# MicroController.net
KiCad netlist of a schematic drawn in Altium Designer
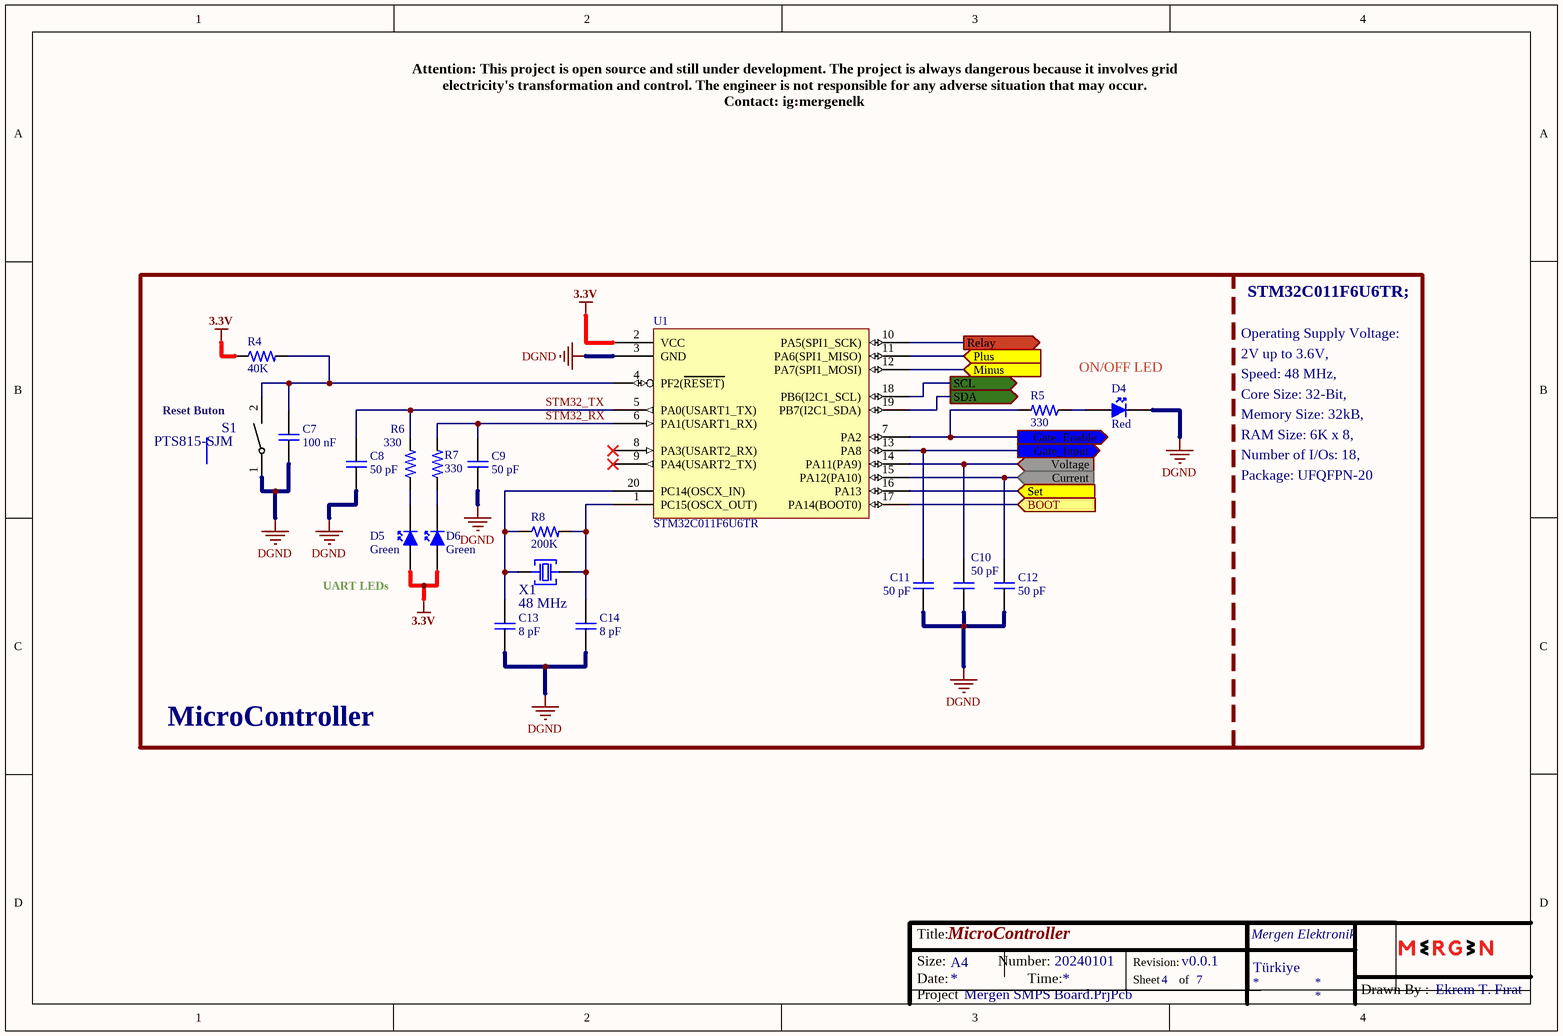
[diagram p0: MicroController.SchDoc]

(export (version "E")
  (design (tool "Eeschema 10.0.6"))
  (components
    (comp (ref "C7")
      (value "100 nF")
      (footprint "MergenElektronik_Capacitors_Ceramics_SMDs_0603_S_NS")
      (description "Mergen Elektronik - Capacitors - Ceramics - SMDs - 0603 - 100 nF - 16V")
      (fields (field (name "MANUFACTURER") "Samsung Electro-Mechanics") (field (name "TOLERANCE") "±10%"))
      (libsource (lib "MergenElektronik_Capacitors_Ceramics_SMDs") (part "MergenElektronik_Capacitors_Ceramic_SMDs_100nF_16V"))
    )
    (comp (ref "C8")
      (value "50 pF")
      (footprint "MergenElektronik_Capacitors_Ceramics_SMDs_0402_S_NS")
      (description "Mergen Elektronik - Capacitors - Ceramics - SMDs - 0402 - 50 pF - 50V")
      (fields (field (name "MANUFACTURER") "YAGEO") (field (name "TOLERANCE") "±5%"))
      (libsource (lib "MergenElektronik_Capacitors_Ceramics_SMDs") (part "MergenElektronik_Capacitors_Ceramic_SMDs_50pF_50V"))
    )
    (comp (ref "C9")
      (value "50 pF")
      (footprint "MergenElektronik_Capacitors_Ceramics_SMDs_0402_S_NS")
      (description "Mergen Elektronik - Capacitors - Ceramics - SMDs - 0402 - 50 pF - 50V")
      (fields (field (name "MANUFACTURER") "YAGEO") (field (name "TOLERANCE") "±5%"))
      (libsource (lib "MergenElektronik_Capacitors_Ceramics_SMDs") (part "MergenElektronik_Capacitors_Ceramic_SMDs_50pF_50V"))
    )
    (comp (ref "C10")
      (value "50 pF")
      (footprint "MergenElektronik_Capacitors_Ceramics_SMDs_0402_S_NS")
      (description "Mergen Elektronik - Capacitors - Ceramics - SMDs - 0402 - 50 pF - 50V")
      (fields (field (name "MANUFACTURER") "YAGEO") (field (name "TOLERANCE") "±5%"))
      (libsource (lib "MergenElektronik_Capacitors_Ceramics_SMDs") (part "MergenElektronik_Capacitors_Ceramic_SMDs_50pF_50V"))
    )
    (comp (ref "C11")
      (value "50 pF")
      (footprint "MergenElektronik_Capacitors_Ceramics_SMDs_0402_S_NS")
      (description "Mergen Elektronik - Capacitors - Ceramics - SMDs - 0402 - 50 pF - 50V")
      (fields (field (name "MANUFACTURER") "YAGEO") (field (name "TOLERANCE") "±5%"))
      (libsource (lib "MergenElektronik_Capacitors_Ceramics_SMDs") (part "MergenElektronik_Capacitors_Ceramic_SMDs_50pF_50V"))
    )
    (comp (ref "C12")
      (value "50 pF")
      (footprint "MergenElektronik_Capacitors_Ceramics_SMDs_0402_S_NS")
      (description "Mergen Elektronik - Capacitors - Ceramics - SMDs - 0402 - 50 pF - 50V")
      (fields (field (name "MANUFACTURER") "YAGEO") (field (name "TOLERANCE") "±5%"))
      (libsource (lib "MergenElektronik_Capacitors_Ceramics_SMDs") (part "MergenElektronik_Capacitors_Ceramic_SMDs_50pF_50V"))
    )
    (comp (ref "C13")
      (value "8 pF")
      (footprint "MergenElektronik_Capacitors_Ceramics_SMDs_0603_S_NS")
      (description "Mergen Elektronik - Capacitors - Ceramics - SMDs - 0603 - 8 pF - 50V")
      (fields (field (name "MANUFACTURER") "YAGEO") (field (name "TOLERANCE") "±0.5pF"))
      (libsource (lib "MergenElektronik_Capacitors_Ceramics_SMDs") (part "MergenElektronik_Capacitors_Ceramic_SMDs_8pF_50V"))
    )
    (comp (ref "C14")
      (value "8 pF")
      (footprint "MergenElektronik_Capacitors_Ceramics_SMDs_0603_S_NS")
      (description "Mergen Elektronik - Capacitors - Ceramics - SMDs - 0603 - 8 pF - 50V")
      (fields (field (name "MANUFACTURER") "YAGEO") (field (name "TOLERANCE") "±0.5pF"))
      (libsource (lib "MergenElektronik_Capacitors_Ceramics_SMDs") (part "MergenElektronik_Capacitors_Ceramic_SMDs_8pF_50V"))
    )
    (comp (ref "D4")
      (value "Red")
      (footprint "MergenElektronik_Leds_SMDs_0603_S")
      (description "Mergen Elektronik - Leds - SMDs - Red - 0603")
      (fields (field (name "MANUFACTURER") "Würth Elektronik"))
      (libsource (lib "MergenElektronik_Leds_SMDs") (part "MergenElektronik_LEDs_SMDs_Red_0603"))
    )
    (comp (ref "D5")
      (value "Green")
      (footprint "MergenElektronik_Leds_SMDs_0603_S")
      (description "Mergen Elektronik - Leds - SMDs - Green - 0603")
      (fields (field (name "MANUFACTURER") "Würth Elektronik"))
      (libsource (lib "MergenElektronik_Leds_SMDs") (part "MergenElektronik_LEDs_SMDs_Green_0603"))
    )
    (comp (ref "D6")
      (value "Green")
      (footprint "MergenElektronik_Leds_SMDs_0603_S")
      (description "Mergen Elektronik - Leds - SMDs - Green - 0603")
      (fields (field (name "MANUFACTURER") "Würth Elektronik"))
      (libsource (lib "MergenElektronik_Leds_SMDs") (part "MergenElektronik_LEDs_SMDs_Green_0603"))
    )
    (comp (ref "R4")
      (value "40K")
      (footprint "MergenElektronik_Resistors_ChipResistors_0603_S_NS")
      (description "Mergen Elektronik - Resistors - Chip Resistors - 0603 - 40K")
      (fields (field (name "MANUFACTURER") "YAGEO") (field (name "POWER") "1/10W"))
      (libsource (lib "MergenElektronik_Resistors_ChipResistors") (part "MergenElektronik_Resistors_ChipResistors_0603_40K"))
    )
    (comp (ref "R5")
      (value "330")
      (footprint "MergenElektronik_Resistors_ChipResistors_0603_S_NS")
      (description "Mergen Elektronik - Resistors - Chip Resistors - 0603 - 330R")
      (fields (field (name "MANUFACTURER") "Stackpole Electronics Inc") (field (name "POWER") "1/10W"))
      (libsource (lib "MergenElektronik_Resistors_ChipResistors") (part "MergenElektronik_Resistors_ChipResistors_0603_330R"))
    )
    (comp (ref "R6")
      (value "330")
      (footprint "MergenElektronik_Resistors_ChipResistors_0603_S_NS")
      (description "Mergen Elektronik - Resistors - Chip Resistors - 0603 - 330R")
      (fields (field (name "MANUFACTURER") "Stackpole Electronics Inc") (field (name "POWER") "1/10W"))
      (libsource (lib "MergenElektronik_Resistors_ChipResistors") (part "MergenElektronik_Resistors_ChipResistors_0603_330R"))
    )
    (comp (ref "R7")
      (value "330")
      (footprint "MergenElektronik_Resistors_ChipResistors_0603_S_NS")
      (description "Mergen Elektronik - Resistors - Chip Resistors - 0603 - 330R")
      (fields (field (name "MANUFACTURER") "Stackpole Electronics Inc") (field (name "POWER") "1/10W"))
      (libsource (lib "MergenElektronik_Resistors_ChipResistors") (part "MergenElektronik_Resistors_ChipResistors_0603_330R"))
    )
    (comp (ref "R8")
      (value "200K")
      (footprint "MergenElektronik_Resistors_ChipResistors_0603_S_NS")
      (description "Mergen Elektronik - Resistors - Chip Resistors - 0603 - 200K")
      (fields (field (name "MANUFACTURER") "Stackpole Electronics Inc") (field (name "POWER") "1/10W"))
      (libsource (lib "MergenElektronik_Resistors_ChipResistors") (part "MergenElektronik_Resistors_ChipResistors_0603_200K"))
    )
    (comp (ref "S1")
      (value "PTS815-SJM")
      (footprint "MergenElektronik_Switches_TactileSwitches_PTS815")
      (description "Mergen Elektronik - Switches - Tactile  Switches")
      (fields (field (name "MANUFACTURER") "C&K"))
      (libsource (lib "MergenElektronik_Switches_TactileSwitches") (part "MergenElektronik_Switches_TactileSwitches_PTS815-SJM"))
    )
    (comp (ref "U1")
      (value "STM32C011F6U6TR")
      (footprint "MergenElektronik_Microcontrollers_STMicroelectronics_UFQFPN-20")
      (description "Mergen Elektronik - Microcontrollers - STMicroelectronics - STM32C011F6U6TR")
      (fields (field (name "MANUFACTURER") "STMicroelectronics"))
      (libsource (lib "MergenElektronik_Microcontrollers_STMicroelectronics") (part "MergenElektronik_Microcontrollers_STMicroelectronics_STM32C011F6U6TR"))
    )
    (comp (ref "X1")
      (value "48 MHz")
      (footprint "MergenElektronik_Oscillators_Crystals_2-SMD")
      (description "Mergen Elektronik - Oscilators - Crystals - 2-SMD - 48 MHz")
      (fields (field (name "MANUFACTURER") "NDK America, Inc."))
      (libsource (lib "MergenElektronik_Oscillators_Crystals") (part "MergenElektronik_Oscillators_Crystals_2_SMD_48MHz"))
    )
  )
  (nets
    (net (code "1") (name "/BOOT") (class "Default")
      (node (ref "U1") (pin "17") (pinfunction "PA14(BOOT0)_17") (pintype "bidirectional"))
    )
    (net (code "2") (name "/Current") (class "Default")
      (node (ref "C12") (pin "1") (pinfunction "1_1") (pintype "passive"))
      (node (ref "U1") (pin "15") (pinfunction "PA12(PA10)_15") (pintype "bidirectional"))
    )
    (net (code "3") (name "/Gate_Enable") (class "Default")
      (node (ref "R5") (pin "2") (pinfunction "2_2") (pintype "passive"))
      (node (ref "U1") (pin "7") (pinfunction "PA2_7") (pintype "bidirectional"))
    )
    (net (code "4") (name "/Gate_Input") (class "Default")
      (node (ref "C11") (pin "1") (pinfunction "1_1") (pintype "passive"))
      (node (ref "U1") (pin "13") (pinfunction "PA8_13") (pintype "bidirectional"))
    )
    (net (code "5") (name "/Minus") (class "Default")
      (node (ref "U1") (pin "12") (pinfunction "PA7(SPI1_MOSI)_12") (pintype "bidirectional"))
    )
    (net (code "6") (name "/Plus") (class "Default")
      (node (ref "U1") (pin "11") (pinfunction "PA6(SPI1_MISO)_11") (pintype "bidirectional"))
    )
    (net (code "7") (name "/Relay") (class "Default")
      (node (ref "U1") (pin "10") (pinfunction "PA5(SPI1_SCK)_10") (pintype "bidirectional"))
    )
    (net (code "8") (name "/SCL") (class "Default")
      (node (ref "U1") (pin "18") (pinfunction "PB6(I2C1_SCL)_18") (pintype "bidirectional"))
    )
    (net (code "9") (name "/SDA") (class "Default")
      (node (ref "U1") (pin "19") (pinfunction "PB7(I2C1_SDA)_19") (pintype "bidirectional"))
    )
    (net (code "10") (name "/STM32_RX") (class "Default")
      (node (ref "C9") (pin "1") (pinfunction "1_1") (pintype "passive"))
      (node (ref "R7") (pin "2") (pinfunction "2_2") (pintype "passive"))
      (node (ref "U1") (pin "6") (pinfunction "PA1(USART1_RX)_6") (pintype "input"))
    )
    (net (code "11") (name "/STM32_TX") (class "Default")
      (node (ref "C8") (pin "1") (pinfunction "1_1") (pintype "passive"))
      (node (ref "R6") (pin "2") (pinfunction "2_2") (pintype "passive"))
      (node (ref "U1") (pin "5") (pinfunction "PA0(USART1_TX)_5") (pintype "output"))
    )
    (net (code "12") (name "/Set") (class "Default")
      (node (ref "U1") (pin "16") (pinfunction "PA13_16") (pintype "bidirectional"))
    )
    (net (code "13") (name "/Voltage") (class "Default")
      (node (ref "C10") (pin "1") (pinfunction "1_1") (pintype "passive"))
      (node (ref "U1") (pin "14") (pinfunction "PA11(PA9)_14") (pintype "bidirectional"))
    )
    (net (code "14") (name "3.3V") (class "Default")
      (node (ref "D5") (pin "1") (pinfunction "ANOT_1") (pintype "passive"))
      (node (ref "D6") (pin "1") (pinfunction "ANOT_1") (pintype "passive"))
      (node (ref "R4") (pin "1") (pinfunction "1_1") (pintype "passive"))
      (node (ref "U1") (pin "2") (pinfunction "VCC_2") (pintype "power_in"))
    )
    (net (code "15") (name "DGND") (class "Default")
      (node (ref "C10") (pin "2") (pinfunction "2_2") (pintype "passive"))
      (node (ref "C11") (pin "2") (pinfunction "2_2") (pintype "passive"))
      (node (ref "C12") (pin "2") (pinfunction "2_2") (pintype "passive"))
      (node (ref "C13") (pin "2") (pinfunction "2_2") (pintype "passive"))
      (node (ref "C14") (pin "2") (pinfunction "2_2") (pintype "passive"))
      (node (ref "C7") (pin "2") (pinfunction "2_2") (pintype "passive"))
      (node (ref "C8") (pin "2") (pinfunction "2_2") (pintype "passive"))
      (node (ref "C9") (pin "2") (pinfunction "2_2") (pintype "passive"))
      (node (ref "D4") (pin "2") (pinfunction "KATOT_2") (pintype "passive"))
      (node (ref "S1") (pin "1") (pinfunction "1_1") (pintype "passive"))
      (node (ref "U1") (pin "3") (pinfunction "GND_3") (pintype "power_in"))
    )
    (net (code "16") (name "Net-(D4-ANOT)") (class "Default")
      (node (ref "D4") (pin "1") (pinfunction "ANOT_1") (pintype "passive"))
      (node (ref "R5") (pin "1") (pinfunction "1_1") (pintype "passive"))
    )
    (net (code "17") (name "Net-(D5-KATOT)") (class "Default")
      (node (ref "D5") (pin "2") (pinfunction "KATOT_2") (pintype "passive"))
      (node (ref "R6") (pin "1") (pinfunction "1_1") (pintype "passive"))
    )
    (net (code "18") (name "Net-(D6-KATOT)") (class "Default")
      (node (ref "D6") (pin "2") (pinfunction "KATOT_2") (pintype "passive"))
      (node (ref "R7") (pin "1") (pinfunction "1_1") (pintype "passive"))
    )
    (net (code "19") (name "Net-(U1-PC14(OSCX_IN))") (class "Default")
      (node (ref "C13") (pin "1") (pinfunction "1_1") (pintype "passive"))
      (node (ref "R8") (pin "1") (pinfunction "1_1") (pintype "passive"))
      (node (ref "U1") (pin "20") (pinfunction "PC14(OSCX_IN)_20") (pintype "passive"))
      (node (ref "X1") (pin "1") (pinfunction "1_1") (pintype "passive"))
    )
    (net (code "20") (name "Net-(U1-PC15(OSCX_OUT))") (class "Default")
      (node (ref "C14") (pin "1") (pinfunction "1_1") (pintype "passive"))
      (node (ref "R8") (pin "2") (pinfunction "2_2") (pintype "passive"))
      (node (ref "U1") (pin "1") (pinfunction "PC15(OSCX_OUT)_1") (pintype "passive"))
      (node (ref "X1") (pin "2") (pinfunction "2_2") (pintype "passive"))
    )
    (net (code "21") (name "Net-(U1-PF2(RESET))") (class "Default")
      (node (ref "C7") (pin "1") (pinfunction "1_1") (pintype "passive"))
      (node (ref "R4") (pin "2") (pinfunction "2_2") (pintype "passive"))
      (node (ref "S1") (pin "2") (pinfunction "2_2") (pintype "passive"))
      (node (ref "U1") (pin "4") (pinfunction "PF2(RESET)_4") (pintype "bidirectional"))
    )
    (net (code "22") (name "unconnected-(U1-PA3(USART2_RX)-Pad8)") (class "Default")
      (node (ref "U1") (pin "8") (pinfunction "PA3(USART2_RX)_8") (pintype "input+no_connect"))
    )
    (net (code "23") (name "unconnected-(U1-PA4(USART2_TX)-Pad9)") (class "Default")
      (node (ref "U1") (pin "9") (pinfunction "PA4(USART2_TX)_9") (pintype "output+no_connect"))
    )
  )
)
